# PiHAT.net
KiCad netlist of a schematic drawn in EAGLE
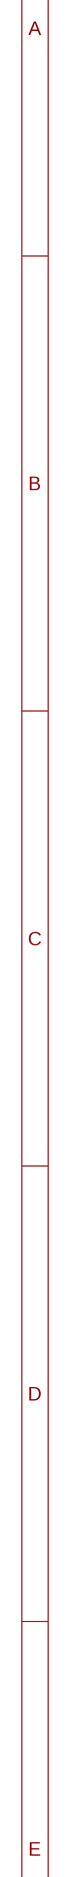
[diagram p0: schematic, sheet 1, part 1 of 2]
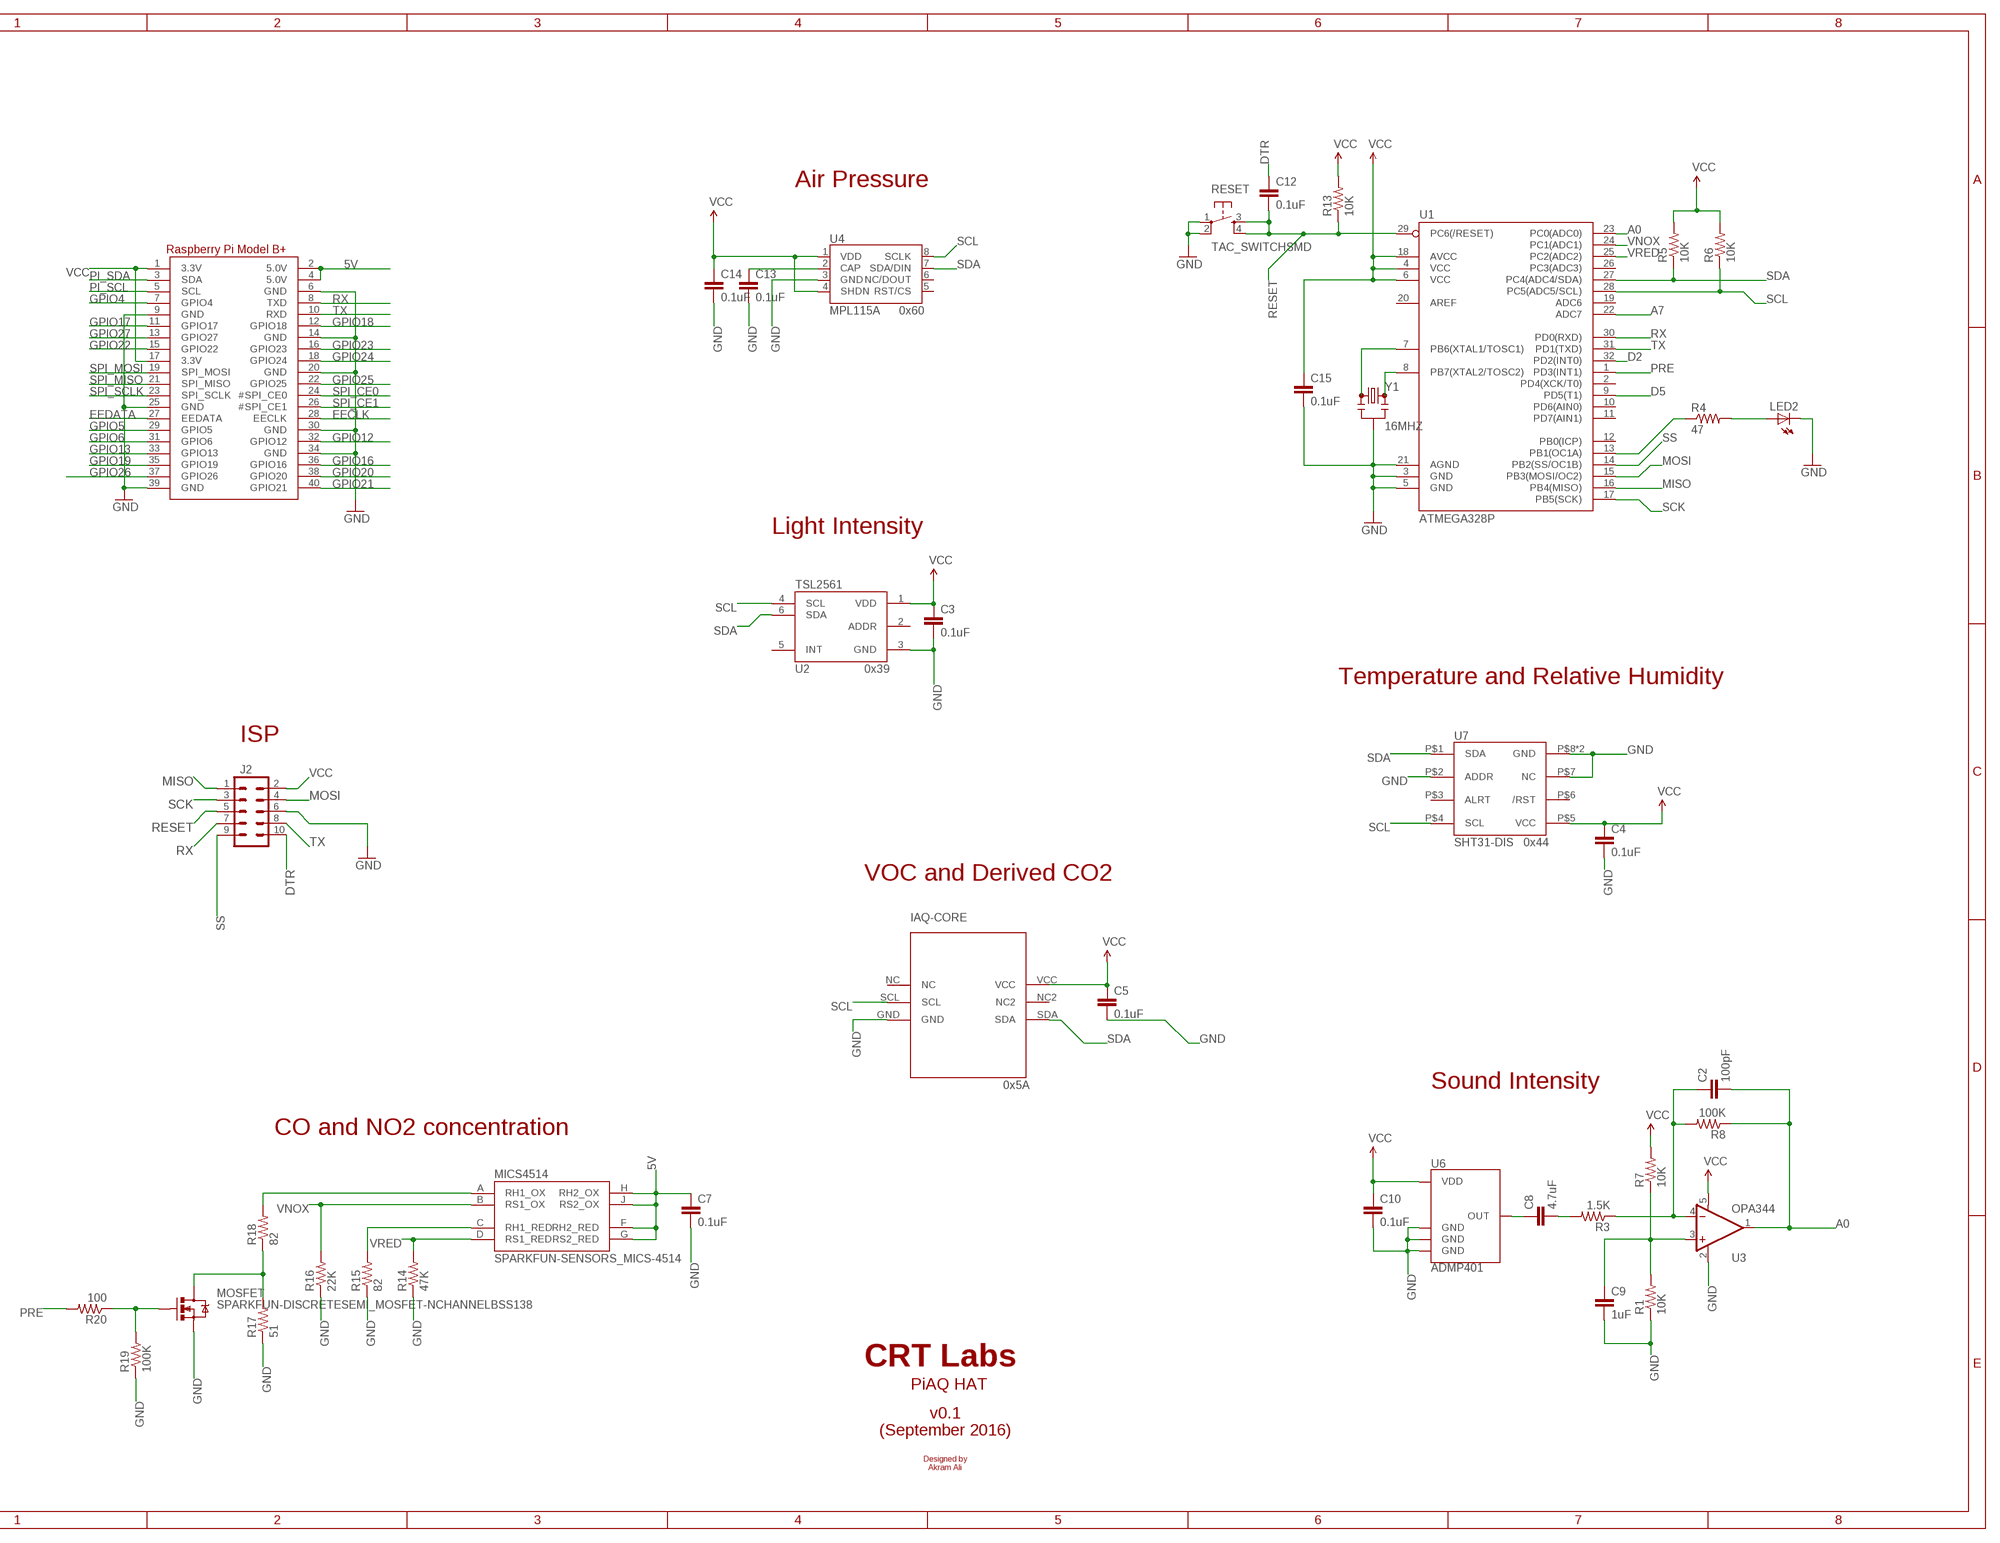
[diagram p1: schematic, sheet 1, part 2 of 2]

(export (version "E")
  (design (tool "Eeschema 10.0.6"))
  (components
    (comp (ref "C2")
      (value "100pF")
      (footprint "eagle-import:0805")
      (libsource (lib "eagle-import") (part "CAP0805"))
    )
    (comp (ref "C3")
      (value "0.1uF")
      (footprint "eagle-import:0805")
      (libsource (lib "eagle-import") (part "SparkFun-Passives_CAP0805"))
    )
    (comp (ref "C4")
      (value "0.1uF")
      (footprint "eagle-import:0805")
      (libsource (lib "eagle-import") (part "SparkFun-Passives_CAP0805"))
    )
    (comp (ref "C5")
      (value "0.1uF")
      (footprint "eagle-import:0805")
      (libsource (lib "eagle-import") (part "SparkFun-Passives_CAP0805"))
    )
    (comp (ref "C7")
      (value "0.1uF")
      (footprint "eagle-import:0805")
      (libsource (lib "eagle-import") (part "SparkFun-Passives_CAP0805"))
    )
    (comp (ref "C8")
      (value "4.7uF")
      (footprint "eagle-import:0805")
      (libsource (lib "eagle-import") (part "CAP0805"))
    )
    (comp (ref "C9")
      (value "1uF")
      (footprint "eagle-import:0805")
      (libsource (lib "eagle-import") (part "CAP0805"))
    )
    (comp (ref "C10")
      (value "0.1uF")
      (footprint "eagle-import:0805")
      (libsource (lib "eagle-import") (part "CAP0805"))
    )
    (comp (ref "C12")
      (value "0.1uF")
      (footprint "eagle-import:0805")
      (libsource (lib "eagle-import") (part "SparkFun-Passives_CAP0805"))
    )
    (comp (ref "C13")
      (value "0.1uF")
      (footprint "eagle-import:0805")
      (libsource (lib "eagle-import") (part "SparkFun-Passives_CAP0805"))
    )
    (comp (ref "C14")
      (value "0.1uF")
      (footprint "eagle-import:0805")
      (libsource (lib "eagle-import") (part "SparkFun-Passives_CAP0805"))
    )
    (comp (ref "C15")
      (value "0.1uF")
      (footprint "eagle-import:0805")
      (libsource (lib "eagle-import") (part "SparkFun-Passives_CAP0805"))
    )
    (comp (ref "IAQ-CORE")
      (value "IAQ-CORE")
      (footprint "eagle-import:IAQ-CORE")
      (fields (field (name "MPN") "IAQ CORE"))
      (libsource (lib "eagle-import") (part "IAQ-CORE"))
    )
    (comp (ref "J2")
      (value "M05X2PTH")
      (footprint "eagle-import:AVR_ICSP")
      (libsource (lib "eagle-import") (part "M05X2PTH"))
    )
    (comp (ref "LED2")
      (value "LEDCHIPLED_0805")
      (footprint "eagle-import:CHIPLED_0805")
      (libsource (lib "eagle-import") (part "LEDCHIPLED_0805"))
    )
    (comp (ref "MICS4514")
      (value "SPARKFUN-SENSORS_MICS-4514")
      (footprint "eagle-import:SPARKFUN-SENSORS_MICS_10-SMD")
      (libsource (lib "eagle-import") (part "SPARKFUN-SENSORS_MICS-4514"))
    )
    (comp (ref "MOSFET")
      (value "SPARKFUN-DISCRETESEMI_MOSFET-NCHANNELBSS138")
      (footprint "eagle-import:SPARKFUN-DISCRETESEMI_SOT23-3")
      (libsource (lib "eagle-import") (part "SPARKFUN-DISCRETESEMI_MOSFET-NCHANNELBSS138"))
    )
    (comp (ref "R1")
      (value "10K")
      (footprint "eagle-import:0805")
      (libsource (lib "eagle-import") (part "RESISTOR0805-RES"))
    )
    (comp (ref "R3")
      (value "1.5K")
      (footprint "eagle-import:0805")
      (libsource (lib "eagle-import") (part "RESISTOR0805-RES"))
    )
    (comp (ref "R4")
      (value "47")
      (footprint "eagle-import:0805")
      (libsource (lib "eagle-import") (part "SparkFun-Resistors_RESISTOR0805-RES"))
    )
    (comp (ref "R5")
      (value "10K")
      (footprint "eagle-import:0805")
      (libsource (lib "eagle-import") (part "SparkFun-Resistors_RESISTOR0805-RES"))
    )
    (comp (ref "R6")
      (value "10K")
      (footprint "eagle-import:0805")
      (libsource (lib "eagle-import") (part "SparkFun-Resistors_RESISTOR0805-RES"))
    )
    (comp (ref "R7")
      (value "10K")
      (footprint "eagle-import:0805")
      (libsource (lib "eagle-import") (part "RESISTOR0805-RES"))
    )
    (comp (ref "R8")
      (value "100K")
      (footprint "eagle-import:0805")
      (libsource (lib "eagle-import") (part "RESISTOR0805-RES"))
    )
    (comp (ref "R13")
      (value "10K")
      (footprint "eagle-import:0805")
      (libsource (lib "eagle-import") (part "RESISTOR0805-RES"))
    )
    (comp (ref "R14")
      (value "47K")
      (footprint "eagle-import:0805")
      (libsource (lib "eagle-import") (part "RESISTOR0805-RES"))
    )
    (comp (ref "R15")
      (value "82")
      (footprint "eagle-import:0805")
      (libsource (lib "eagle-import") (part "RESISTOR0805-RES"))
    )
    (comp (ref "R16")
      (value "22K")
      (footprint "eagle-import:0805")
      (libsource (lib "eagle-import") (part "RESISTOR0805-RES"))
    )
    (comp (ref "R17")
      (value "51")
      (footprint "eagle-import:0805")
      (libsource (lib "eagle-import") (part "RESISTOR0805-RES"))
    )
    (comp (ref "R18")
      (value "82")
      (footprint "eagle-import:0805")
      (libsource (lib "eagle-import") (part "RESISTOR0805-RES"))
    )
    (comp (ref "R19")
      (value "100K")
      (footprint "eagle-import:0805")
      (libsource (lib "eagle-import") (part "RESISTOR0805-RES"))
    )
    (comp (ref "R20")
      (value "100")
      (footprint "eagle-import:0805")
      (libsource (lib "eagle-import") (part "RESISTOR0805-RES"))
    )
    (comp (ref "RESET")
      (value "TAC_SWITCHSMD")
      (footprint "eagle-import:TACTILE-SWITCH-SMD")
      (libsource (lib "eagle-import") (part "TAC_SWITCHSMD"))
    )
    (comp (ref "RPI1")
      (value "RASPBERRYPI_BPLUS_HATSLOTS")
      (footprint "eagle-import:PI_HAT_SLOTS")
      (libsource (lib "eagle-import") (part "RASPBERRYPI_BPLUS_HATSLOTS"))
    )
    (comp (ref "U1")
      (value "ATMEGA328P")
      (footprint "eagle-import:TQFP32-08")
      (fields (field (name "MPN") "ATMEGA328PB-AU"))
      (libsource (lib "eagle-import") (part "ATMEGA328P_TQFP"))
    )
    (comp (ref "U2")
      (value "TSL2561")
      (footprint "eagle-import:FN-6")
      (fields (field (name "MANF") "AMS-TAOS-USA-Inc.") (field (name "MPN") "TSL2561FN"))
      (libsource (lib "eagle-import") (part "TSL2561FN"))
    )
    (comp (ref "U3")
      (value "OPA344")
      (footprint "eagle-import:SOT23-5")
      (libsource (lib "eagle-import") (part "OPA344"))
    )
    (comp (ref "U4")
      (value "MPL115A")
      (footprint "eagle-import:LGA8")
      (libsource (lib "eagle-import") (part "MPL115A"))
    )
    (comp (ref "U6")
      (value "ADMP401")
      (footprint "eagle-import:ADMP401")
      (libsource (lib "eagle-import") (part "ADMP401"))
    )
    (comp (ref "U7")
      (value "SHT31-DIS")
      (footprint "eagle-import:SHT3X")
      (fields (field (name "MPN") "SHT31-DIS-B"))
      (libsource (lib "eagle-import") (part "SHT31-DIS"))
    )
    (comp (ref "Y1")
      (value "16MHZ")
      (footprint "eagle-import:RESONATOR-SMD")
      (libsource (lib "eagle-import") (part "RESONATOR16MHZ"))
    )
  )
  (nets
    (net (code "1") (name "/EECLK") (class "Default")
      (node (ref "RPI1") (pin "28") (pinfunction "EECLK_28") (pintype "power_in"))
    )
    (net (code "2") (name "/EEDATA") (class "Default")
      (node (ref "RPI1") (pin "27") (pinfunction "EEDATA_27") (pintype "bidirectional"))
    )
    (net (code "3") (name "/GPIO4") (class "Default")
      (node (ref "RPI1") (pin "7") (pinfunction "GPIO4_7") (pintype "bidirectional"))
    )
    (net (code "4") (name "/GPIO5") (class "Default")
      (node (ref "RPI1") (pin "29") (pinfunction "GPIO5_29") (pintype "bidirectional"))
    )
    (net (code "5") (name "/GPIO6") (class "Default")
      (node (ref "RPI1") (pin "31") (pinfunction "GPIO6_31") (pintype "power_in"))
    )
    (net (code "6") (name "/GPIO12") (class "Default")
      (node (ref "RPI1") (pin "32") (pinfunction "GPIO12_32") (pintype "bidirectional"))
    )
    (net (code "7") (name "/GPIO13") (class "Default")
      (node (ref "RPI1") (pin "33") (pinfunction "GPIO13_33") (pintype "bidirectional"))
    )
    (net (code "8") (name "/GPIO16") (class "Default")
      (node (ref "RPI1") (pin "36") (pinfunction "GPIO16_36") (pintype "power_in"))
    )
    (net (code "9") (name "/GPIO17") (class "Default")
      (node (ref "RPI1") (pin "11") (pinfunction "GPIO17_11") (pintype "bidirectional"))
    )
    (net (code "10") (name "/GPIO18") (class "Default")
      (node (ref "RPI1") (pin "12") (pinfunction "GPIO18_12") (pintype "bidirectional"))
    )
    (net (code "11") (name "/GPIO19") (class "Default")
      (node (ref "RPI1") (pin "35") (pinfunction "GPIO19_35") (pintype "bidirectional"))
    )
    (net (code "12") (name "/GPIO20") (class "Default")
      (node (ref "RPI1") (pin "38") (pinfunction "GPIO20_38") (pintype "bidirectional"))
    )
    (net (code "13") (name "/GPIO21") (class "Default")
      (node (ref "RPI1") (pin "40") (pinfunction "GPIO21_40") (pintype "bidirectional"))
    )
    (net (code "14") (name "/GPIO22") (class "Default")
      (node (ref "RPI1") (pin "15") (pinfunction "GPIO22_15") (pintype "bidirectional"))
    )
    (net (code "15") (name "/GPIO23") (class "Default")
      (node (ref "RPI1") (pin "16") (pinfunction "GPIO23_16") (pintype "bidirectional"))
    )
    (net (code "16") (name "/GPIO24") (class "Default")
      (node (ref "RPI1") (pin "18") (pinfunction "GPIO24_18") (pintype "bidirectional"))
    )
    (net (code "17") (name "/GPIO25") (class "Default")
      (node (ref "RPI1") (pin "22") (pinfunction "GPIO25_22") (pintype "bidirectional"))
    )
    (net (code "18") (name "/GPIO26") (class "Default")
      (node (ref "RPI1") (pin "37") (pinfunction "GPIO26_37") (pintype "bidirectional"))
    )
    (net (code "19") (name "/GPIO27") (class "Default")
      (node (ref "RPI1") (pin "13") (pinfunction "GPIO27_13") (pintype "bidirectional"))
    )
    (net (code "20") (name "/PI_SCL") (class "Default")
      (node (ref "RPI1") (pin "5") (pinfunction "SCL_5") (pintype "bidirectional"))
    )
    (net (code "21") (name "/PI_SDA") (class "Default")
      (node (ref "RPI1") (pin "3") (pinfunction "SDA_3") (pintype "bidirectional"))
    )
    (net (code "22") (name "/SPI_CE0") (class "Default")
      (node (ref "RPI1") (pin "24") (pinfunction "#SPI_CE0_24") (pintype "bidirectional"))
    )
    (net (code "23") (name "/SPI_CE1") (class "Default")
      (node (ref "RPI1") (pin "26") (pinfunction "#SPI_CE1_26") (pintype "bidirectional"))
    )
    (net (code "24") (name "/SPI_MISO") (class "Default")
      (node (ref "RPI1") (pin "21") (pinfunction "SPI_MISO_21") (pintype "bidirectional"))
    )
    (net (code "25") (name "/SPI_MOSI") (class "Default")
      (node (ref "RPI1") (pin "19") (pinfunction "SPI_MOSI_19") (pintype "bidirectional"))
    )
    (net (code "26") (name "/SPI_SCLK") (class "Default")
      (node (ref "RPI1") (pin "23") (pinfunction "SPI_SCLK_23") (pintype "bidirectional"))
    )
    (net (code "27") (name "5V") (class "Default")
      (node (ref "C7") (pin "1") (pinfunction "1_1") (pintype "passive"))
      (node (ref "MICS4514") (pin "F") (pinfunction "RH2_RED_F") (pintype "bidirectional"))
      (node (ref "MICS4514") (pin "G") (pinfunction "RS2_RED_G") (pintype "bidirectional"))
      (node (ref "MICS4514") (pin "H") (pinfunction "RH2_OX_H") (pintype "bidirectional"))
      (node (ref "MICS4514") (pin "J") (pinfunction "RS2_OX_J") (pintype "bidirectional"))
      (node (ref "RPI1") (pin "2") (pinfunction "5.0V_2") (pintype "power_in"))
      (node (ref "RPI1") (pin "4") (pinfunction "5.0V_4") (pintype "power_in"))
    )
    (net (code "28") (name "A0") (class "Default")
      (node (ref "C2") (pin "2") (pinfunction "2_2") (pintype "passive"))
      (node (ref "R8") (pin "1") (pinfunction "1_1") (pintype "passive"))
      (node (ref "U1") (pin "23") (pinfunction "PC0(ADC0)_23") (pintype "bidirectional"))
      (node (ref "U3") (pin "1") (pinfunction "OUT_1") (pintype "output"))
    )
    (net (code "29") (name "A7") (class "Default")
      (node (ref "U1") (pin "22") (pinfunction "ADC7_22") (pintype "bidirectional"))
    )
    (net (code "30") (name "D2") (class "Default")
      (node (ref "U1") (pin "32") (pinfunction "PD2(INT0)_32") (pintype "bidirectional"))
    )
    (net (code "31") (name "D5") (class "Default")
      (node (ref "U1") (pin "9") (pinfunction "PD5(T1)_9") (pintype "bidirectional"))
    )
    (net (code "32") (name "DTR") (class "Default")
      (node (ref "C12") (pin "1") (pinfunction "1_1") (pintype "passive"))
      (node (ref "J2") (pin "10") (pinfunction "10_10") (pintype "passive"))
    )
    (net (code "33") (name "GND") (class "Default")
      (node (ref "C10") (pin "2") (pinfunction "2_2") (pintype "passive"))
      (node (ref "C13") (pin "2") (pinfunction "2_2") (pintype "passive"))
      (node (ref "C14") (pin "2") (pinfunction "2_2") (pintype "passive"))
      (node (ref "C15") (pin "2") (pinfunction "2_2") (pintype "passive"))
      (node (ref "C3") (pin "2") (pinfunction "2_2") (pintype "passive"))
      (node (ref "C4") (pin "2") (pinfunction "2_2") (pintype "passive"))
      (node (ref "C5") (pin "2") (pinfunction "2_2") (pintype "passive"))
      (node (ref "C7") (pin "2") (pinfunction "2_2") (pintype "passive"))
      (node (ref "C9") (pin "2") (pinfunction "2_2") (pintype "passive"))
      (node (ref "IAQ-CORE") (pin "GND") (pinfunction "GND_GND") (pintype "bidirectional"))
      (node (ref "J2") (pin "6") (pinfunction "6_6") (pintype "passive"))
      (node (ref "LED2") (pin "C") (pinfunction "C_C") (pintype "passive"))
      (node (ref "MOSFET") (pin "2") (pinfunction "S_2") (pintype "passive"))
      (node (ref "R1") (pin "1") (pinfunction "1_1") (pintype "passive"))
      (node (ref "R14") (pin "1") (pinfunction "1_1") (pintype "passive"))
      (node (ref "R15") (pin "1") (pinfunction "1_1") (pintype "passive"))
      (node (ref "R16") (pin "1") (pinfunction "1_1") (pintype "passive"))
      (node (ref "R17") (pin "1") (pinfunction "1_1") (pintype "passive"))
      (node (ref "R19") (pin "1") (pinfunction "1_1") (pintype "passive"))
      (node (ref "RESET") (pin "1") (pinfunction "1_1") (pintype "passive"))
      (node (ref "RESET") (pin "2") (pinfunction "2_2") (pintype "passive"))
      (node (ref "RPI1") (pin "14") (pinfunction "GND_14") (pintype "power_in"))
      (node (ref "RPI1") (pin "20") (pinfunction "GND_20") (pintype "power_in"))
      (node (ref "RPI1") (pin "25") (pinfunction "GND_25") (pintype "power_in"))
      (node (ref "RPI1") (pin "30") (pinfunction "GND_30") (pintype "bidirectional"))
      (node (ref "RPI1") (pin "34") (pinfunction "GND_34") (pintype "bidirectional"))
      (node (ref "RPI1") (pin "39") (pinfunction "GND_39") (pintype "power_in"))
      (node (ref "RPI1") (pin "6") (pinfunction "GND_6") (pintype "power_in"))
      (node (ref "RPI1") (pin "9") (pinfunction "GND_9") (pintype "power_in"))
      (node (ref "U1") (pin "21") (pinfunction "AGND_21") (pintype "bidirectional"))
      (node (ref "U1") (pin "3") (pinfunction "GND_3") (pintype "bidirectional"))
      (node (ref "U1") (pin "5") (pinfunction "GND_5") (pintype "bidirectional"))
      (node (ref "U2") (pin "3") (pinfunction "GND_3") (pintype "power_in"))
      (node (ref "U3") (pin "2") (pinfunction "V-_2") (pintype "power_in"))
      (node (ref "U4") (pin "3") (pinfunction "GND_3") (pintype "bidirectional"))
      (node (ref "U6") (pin "2") (pinfunction "GND_2") (pintype "bidirectional"))
      (node (ref "U6") (pin "4") (pinfunction "GND_4") (pintype "bidirectional"))
      (node (ref "U6") (pin "6") (pinfunction "GND_6") (pintype "bidirectional"))
      (node (ref "U7") (pin "P$2") (pinfunction "ADDR_P$2") (pintype "bidirectional"))
      (node (ref "U7") (pin "P$7") (pinfunction "NC_P$7") (pintype "bidirectional"))
      (node (ref "U7") (pin "P$8") (pinfunction "GND_P$8") (pintype "bidirectional"))
      (node (ref "U7") (pin "PAD") (pinfunction "GND_PAD") (pintype "bidirectional"))
      (node (ref "Y1") (pin "2") (pinfunction "2_2") (pintype "passive"))
    )
    (net (code "34") (name "MISO") (class "Default")
      (node (ref "J2") (pin "1") (pinfunction "1_1") (pintype "passive"))
      (node (ref "U1") (pin "16") (pinfunction "PB4(MISO)_16") (pintype "bidirectional"))
    )
    (net (code "35") (name "MOSI") (class "Default")
      (node (ref "J2") (pin "4") (pinfunction "4_4") (pintype "passive"))
      (node (ref "U1") (pin "15") (pinfunction "PB3(MOSI/OC2)_15") (pintype "bidirectional"))
    )
    (net (code "36") (name "Net-(C8-Pad2)") (class "Default")
      (node (ref "C8") (pin "2") (pinfunction "2_2") (pintype "passive"))
      (node (ref "R3") (pin "2") (pinfunction "2_2") (pintype "passive"))
    )
    (net (code "37") (name "Net-(LED2-PadA)") (class "Default")
      (node (ref "LED2") (pin "A") (pinfunction "A_A") (pintype "passive"))
      (node (ref "R4") (pin "2") (pinfunction "2_2") (pintype "passive"))
    )
    (net (code "38") (name "Net-(MICS4514-RH1_OX)") (class "Default")
      (node (ref "MICS4514") (pin "A") (pinfunction "RH1_OX_A") (pintype "bidirectional"))
      (node (ref "R18") (pin "2") (pinfunction "2_2") (pintype "passive"))
    )
    (net (code "39") (name "Net-(MICS4514-RH1_RED)") (class "Default")
      (node (ref "MICS4514") (pin "C") (pinfunction "RH1_RED_C") (pintype "bidirectional"))
      (node (ref "R15") (pin "2") (pinfunction "2_2") (pintype "passive"))
    )
    (net (code "40") (name "Net-(MOSFET-D)") (class "Default")
      (node (ref "MOSFET") (pin "3") (pinfunction "D_3") (pintype "passive"))
      (node (ref "R17") (pin "2") (pinfunction "2_2") (pintype "passive"))
      (node (ref "R18") (pin "1") (pinfunction "1_1") (pintype "passive"))
    )
    (net (code "41") (name "Net-(MOSFET-G)") (class "Default")
      (node (ref "MOSFET") (pin "1") (pinfunction "G_1") (pintype "passive"))
      (node (ref "R19") (pin "2") (pinfunction "2_2") (pintype "passive"))
      (node (ref "R20") (pin "1") (pinfunction "1_1") (pintype "passive"))
    )
    (net (code "42") (name "Net-(U1-PB1(OC1A))") (class "Default")
      (node (ref "R4") (pin "1") (pinfunction "1_1") (pintype "passive"))
      (node (ref "U1") (pin "13") (pinfunction "PB1(OC1A)_13") (pintype "bidirectional"))
    )
    (net (code "43") (name "Net-(U1-PB6(XTAL1{slash}TOSC1))") (class "Default")
      (node (ref "U1") (pin "7") (pinfunction "PB6(XTAL1/TOSC1)_7") (pintype "bidirectional"))
      (node (ref "Y1") (pin "1") (pinfunction "1_1") (pintype "passive"))
    )
    (net (code "44") (name "Net-(U1-PB7(XTAL2{slash}TOSC2))") (class "Default")
      (node (ref "U1") (pin "8") (pinfunction "PB7(XTAL2/TOSC2)_8") (pintype "bidirectional"))
      (node (ref "Y1") (pin "3") (pinfunction "3_3") (pintype "passive"))
    )
    (net (code "45") (name "Net-(U3-+IN)") (class "Default")
      (node (ref "C9") (pin "1") (pinfunction "1_1") (pintype "passive"))
      (node (ref "R1") (pin "2") (pinfunction "2_2") (pintype "passive"))
      (node (ref "R7") (pin "1") (pinfunction "1_1") (pintype "passive"))
      (node (ref "U3") (pin "3") (pinfunction "+IN_3") (pintype "input"))
    )
    (net (code "46") (name "Net-(U3--IN)") (class "Default")
      (node (ref "C2") (pin "1") (pinfunction "1_1") (pintype "passive"))
      (node (ref "R3") (pin "1") (pinfunction "1_1") (pintype "passive"))
      (node (ref "R8") (pin "2") (pinfunction "2_2") (pintype "passive"))
      (node (ref "U3") (pin "4") (pinfunction "-IN_4") (pintype "input"))
    )
    (net (code "47") (name "Net-(U4-CAP)") (class "Default")
      (node (ref "C13") (pin "1") (pinfunction "1_1") (pintype "passive"))
      (node (ref "U4") (pin "2") (pinfunction "CAP_2") (pintype "bidirectional"))
    )
    (net (code "48") (name "Net-(U6-OUT)") (class "Default")
      (node (ref "C8") (pin "1") (pinfunction "1_1") (pintype "passive"))
      (node (ref "U6") (pin "1") (pinfunction "OUT_1") (pintype "bidirectional"))
    )
    (net (code "49") (name "PRE") (class "Default")
      (node (ref "R20") (pin "2") (pinfunction "2_2") (pintype "passive"))
      (node (ref "U1") (pin "1") (pinfunction "PD3(INT1)_1") (pintype "bidirectional"))
    )
    (net (code "50") (name "RESET") (class "Default")
      (node (ref "C12") (pin "2") (pinfunction "2_2") (pintype "passive"))
      (node (ref "J2") (pin "5") (pinfunction "5_5") (pintype "passive"))
      (node (ref "R13") (pin "1") (pinfunction "1_1") (pintype "passive"))
      (node (ref "RESET") (pin "3") (pinfunction "3_3") (pintype "passive"))
      (node (ref "RESET") (pin "4") (pinfunction "4_4") (pintype "passive"))
      (node (ref "U1") (pin "29") (pinfunction "PC6(/RESET)_29") (pintype "bidirectional"))
    )
    (net (code "51") (name "RX") (class "Default")
      (node (ref "J2") (pin "7") (pinfunction "7_7") (pintype "passive"))
      (node (ref "RPI1") (pin "8") (pinfunction "TXD_8") (pintype "output"))
      (node (ref "U1") (pin "30") (pinfunction "PD0(RXD)_30") (pintype "bidirectional"))
    )
    (net (code "52") (name "SCK") (class "Default")
      (node (ref "J2") (pin "3") (pinfunction "3_3") (pintype "passive"))
      (node (ref "U1") (pin "17") (pinfunction "PB5(SCK)_17") (pintype "bidirectional"))
    )
    (net (code "53") (name "SCL") (class "Default")
      (node (ref "IAQ-CORE") (pin "SCL") (pinfunction "SCL_SCL") (pintype "bidirectional"))
      (node (ref "R6") (pin "1") (pinfunction "1_1") (pintype "passive"))
      (node (ref "U1") (pin "28") (pinfunction "PC5(ADC5/SCL)_28") (pintype "bidirectional"))
      (node (ref "U2") (pin "4") (pinfunction "SCL_4") (pintype "input"))
      (node (ref "U4") (pin "8") (pinfunction "SCLK_8") (pintype "bidirectional"))
      (node (ref "U7") (pin "P$4") (pinfunction "SCL_P$4") (pintype "bidirectional"))
    )
    (net (code "54") (name "SDA") (class "Default")
      (node (ref "IAQ-CORE") (pin "SDA") (pinfunction "SDA_SDA") (pintype "bidirectional"))
      (node (ref "R5") (pin "1") (pinfunction "1_1") (pintype "passive"))
      (node (ref "U1") (pin "27") (pinfunction "PC4(ADC4/SDA)_27") (pintype "bidirectional"))
      (node (ref "U2") (pin "6") (pinfunction "SDA_6") (pintype "bidirectional"))
      (node (ref "U4") (pin "7") (pinfunction "SDA/DIN_7") (pintype "bidirectional"))
      (node (ref "U7") (pin "P$1") (pinfunction "SDA_P$1") (pintype "bidirectional"))
    )
    (net (code "55") (name "SS") (class "Default")
      (node (ref "J2") (pin "9") (pinfunction "9_9") (pintype "passive"))
      (node (ref "U1") (pin "14") (pinfunction "PB2(SS/OC1B)_14") (pintype "bidirectional"))
    )
    (net (code "56") (name "TX") (class "Default")
      (node (ref "J2") (pin "8") (pinfunction "8_8") (pintype "passive"))
      (node (ref "RPI1") (pin "10") (pinfunction "RXD_10") (pintype "bidirectional"))
      (node (ref "U1") (pin "31") (pinfunction "PD1(TXD)_31") (pintype "bidirectional"))
    )
    (net (code "57") (name "VCC") (class "Default")
      (node (ref "C10") (pin "1") (pinfunction "1_1") (pintype "passive"))
      (node (ref "C14") (pin "1") (pinfunction "1_1") (pintype "passive"))
      (node (ref "C15") (pin "1") (pinfunction "1_1") (pintype "passive"))
      (node (ref "C3") (pin "1") (pinfunction "1_1") (pintype "passive"))
      (node (ref "C4") (pin "1") (pinfunction "1_1") (pintype "passive"))
      (node (ref "C5") (pin "1") (pinfunction "1_1") (pintype "passive"))
      (node (ref "IAQ-CORE") (pin "VCC") (pinfunction "VCC_VCC") (pintype "bidirectional"))
      (node (ref "J2") (pin "2") (pinfunction "2_2") (pintype "passive"))
      (node (ref "R13") (pin "2") (pinfunction "2_2") (pintype "passive"))
      (node (ref "R5") (pin "2") (pinfunction "2_2") (pintype "passive"))
      (node (ref "R6") (pin "2") (pinfunction "2_2") (pintype "passive"))
      (node (ref "R7") (pin "2") (pinfunction "2_2") (pintype "passive"))
      (node (ref "RPI1") (pin "1") (pinfunction "3.3V_1") (pintype "power_in"))
      (node (ref "RPI1") (pin "17") (pinfunction "3.3V_17") (pintype "power_in"))
      (node (ref "U1") (pin "18") (pinfunction "AVCC_18") (pintype "bidirectional"))
      (node (ref "U1") (pin "4") (pinfunction "VCC_4") (pintype "bidirectional"))
      (node (ref "U1") (pin "6") (pinfunction "VCC_6") (pintype "bidirectional"))
      (node (ref "U2") (pin "1") (pinfunction "VDD_1") (pintype "power_in"))
      (node (ref "U3") (pin "5") (pinfunction "V+_5") (pintype "power_in"))
      (node (ref "U4") (pin "1") (pinfunction "VDD_1") (pintype "bidirectional"))
      (node (ref "U4") (pin "4") (pinfunction "SHDN_4") (pintype "bidirectional"))
      (node (ref "U6") (pin "5") (pinfunction "VDD_5") (pintype "bidirectional"))
      (node (ref "U7") (pin "P$5") (pinfunction "VCC_P$5") (pintype "bidirectional"))
    )
    (net (code "58") (name "VNOX") (class "Default")
      (node (ref "MICS4514") (pin "B") (pinfunction "RS1_OX_B") (pintype "bidirectional"))
      (node (ref "R16") (pin "2") (pinfunction "2_2") (pintype "passive"))
      (node (ref "U1") (pin "24") (pinfunction "PC1(ADC1)_24") (pintype "bidirectional"))
    )
    (net (code "59") (name "VRED") (class "Default")
      (node (ref "MICS4514") (pin "D") (pinfunction "RS1_RED_D") (pintype "bidirectional"))
      (node (ref "R14") (pin "2") (pinfunction "2_2") (pintype "passive"))
      (node (ref "U1") (pin "25") (pinfunction "PC2(ADC2)_25") (pintype "bidirectional"))
    )
    (net (code "60") (name "unconnected-(IAQ-CORE-PadNC)") (class "Default")
      (node (ref "IAQ-CORE") (pin "NC") (pinfunction "NC_NC") (pintype "bidirectional"))
    )
    (net (code "61") (name "unconnected-(IAQ-CORE-PadNC2)") (class "Default")
      (node (ref "IAQ-CORE") (pin "NC2") (pinfunction "NC2_NC2") (pintype "bidirectional"))
    )
    (net (code "62") (name "unconnected-(U1-ADC6-Pad19)") (class "Default")
      (node (ref "U1") (pin "19") (pinfunction "ADC6_19") (pintype "bidirectional"))
    )
    (net (code "63") (name "unconnected-(U1-AREF-Pad20)") (class "Default")
      (node (ref "U1") (pin "20") (pinfunction "AREF_20") (pintype "bidirectional"))
    )
    (net (code "64") (name "unconnected-(U1-PB0(ICP)-Pad12)") (class "Default")
      (node (ref "U1") (pin "12") (pinfunction "PB0(ICP)_12") (pintype "bidirectional"))
    )
    (net (code "65") (name "unconnected-(U1-PC3(ADC3)-Pad26)") (class "Default")
      (node (ref "U1") (pin "26") (pinfunction "PC3(ADC3)_26") (pintype "bidirectional"))
    )
    (net (code "66") (name "unconnected-(U1-PD4(XCK{slash}T0)-Pad2)") (class "Default")
      (node (ref "U1") (pin "2") (pinfunction "PD4(XCK/T0)_2") (pintype "bidirectional"))
    )
    (net (code "67") (name "unconnected-(U1-PD6(AIN0)-Pad10)") (class "Default")
      (node (ref "U1") (pin "10") (pinfunction "PD6(AIN0)_10") (pintype "bidirectional"))
    )
    (net (code "68") (name "unconnected-(U1-PD7(AIN1)-Pad11)") (class "Default")
      (node (ref "U1") (pin "11") (pinfunction "PD7(AIN1)_11") (pintype "bidirectional"))
    )
    (net (code "69") (name "unconnected-(U2-ADDR-Pad2)") (class "Default")
      (node (ref "U2") (pin "2") (pinfunction "ADDR_2") (pintype "input"))
    )
    (net (code "70") (name "unconnected-(U2-INT-Pad5)") (class "Default")
      (node (ref "U2") (pin "5") (pinfunction "INT_5") (pintype "output"))
    )
    (net (code "71") (name "unconnected-(U4-NC{slash}DOUT-Pad6)") (class "Default")
      (node (ref "U4") (pin "6") (pinfunction "NC/DOUT_6") (pintype "bidirectional"))
    )
    (net (code "72") (name "unconnected-(U4-RST{slash}CS-Pad5)") (class "Default")
      (node (ref "U4") (pin "5") (pinfunction "RST/CS_5") (pintype "bidirectional"))
    )
    (net (code "73") (name "unconnected-(U7-ALRT-PadP$3)") (class "Default")
      (node (ref "U7") (pin "P$3") (pinfunction "ALRT_P$3") (pintype "bidirectional"))
    )
    (net (code "74") (name "unconnected-(U7-{slash}RST-PadP$6)") (class "Default")
      (node (ref "U7") (pin "P$6") (pinfunction "/RST_P$6") (pintype "bidirectional"))
    )
  )
)
